# MCU_STM32F446RE.net
KiCad netlist of a schematic drawn in Altium Designer
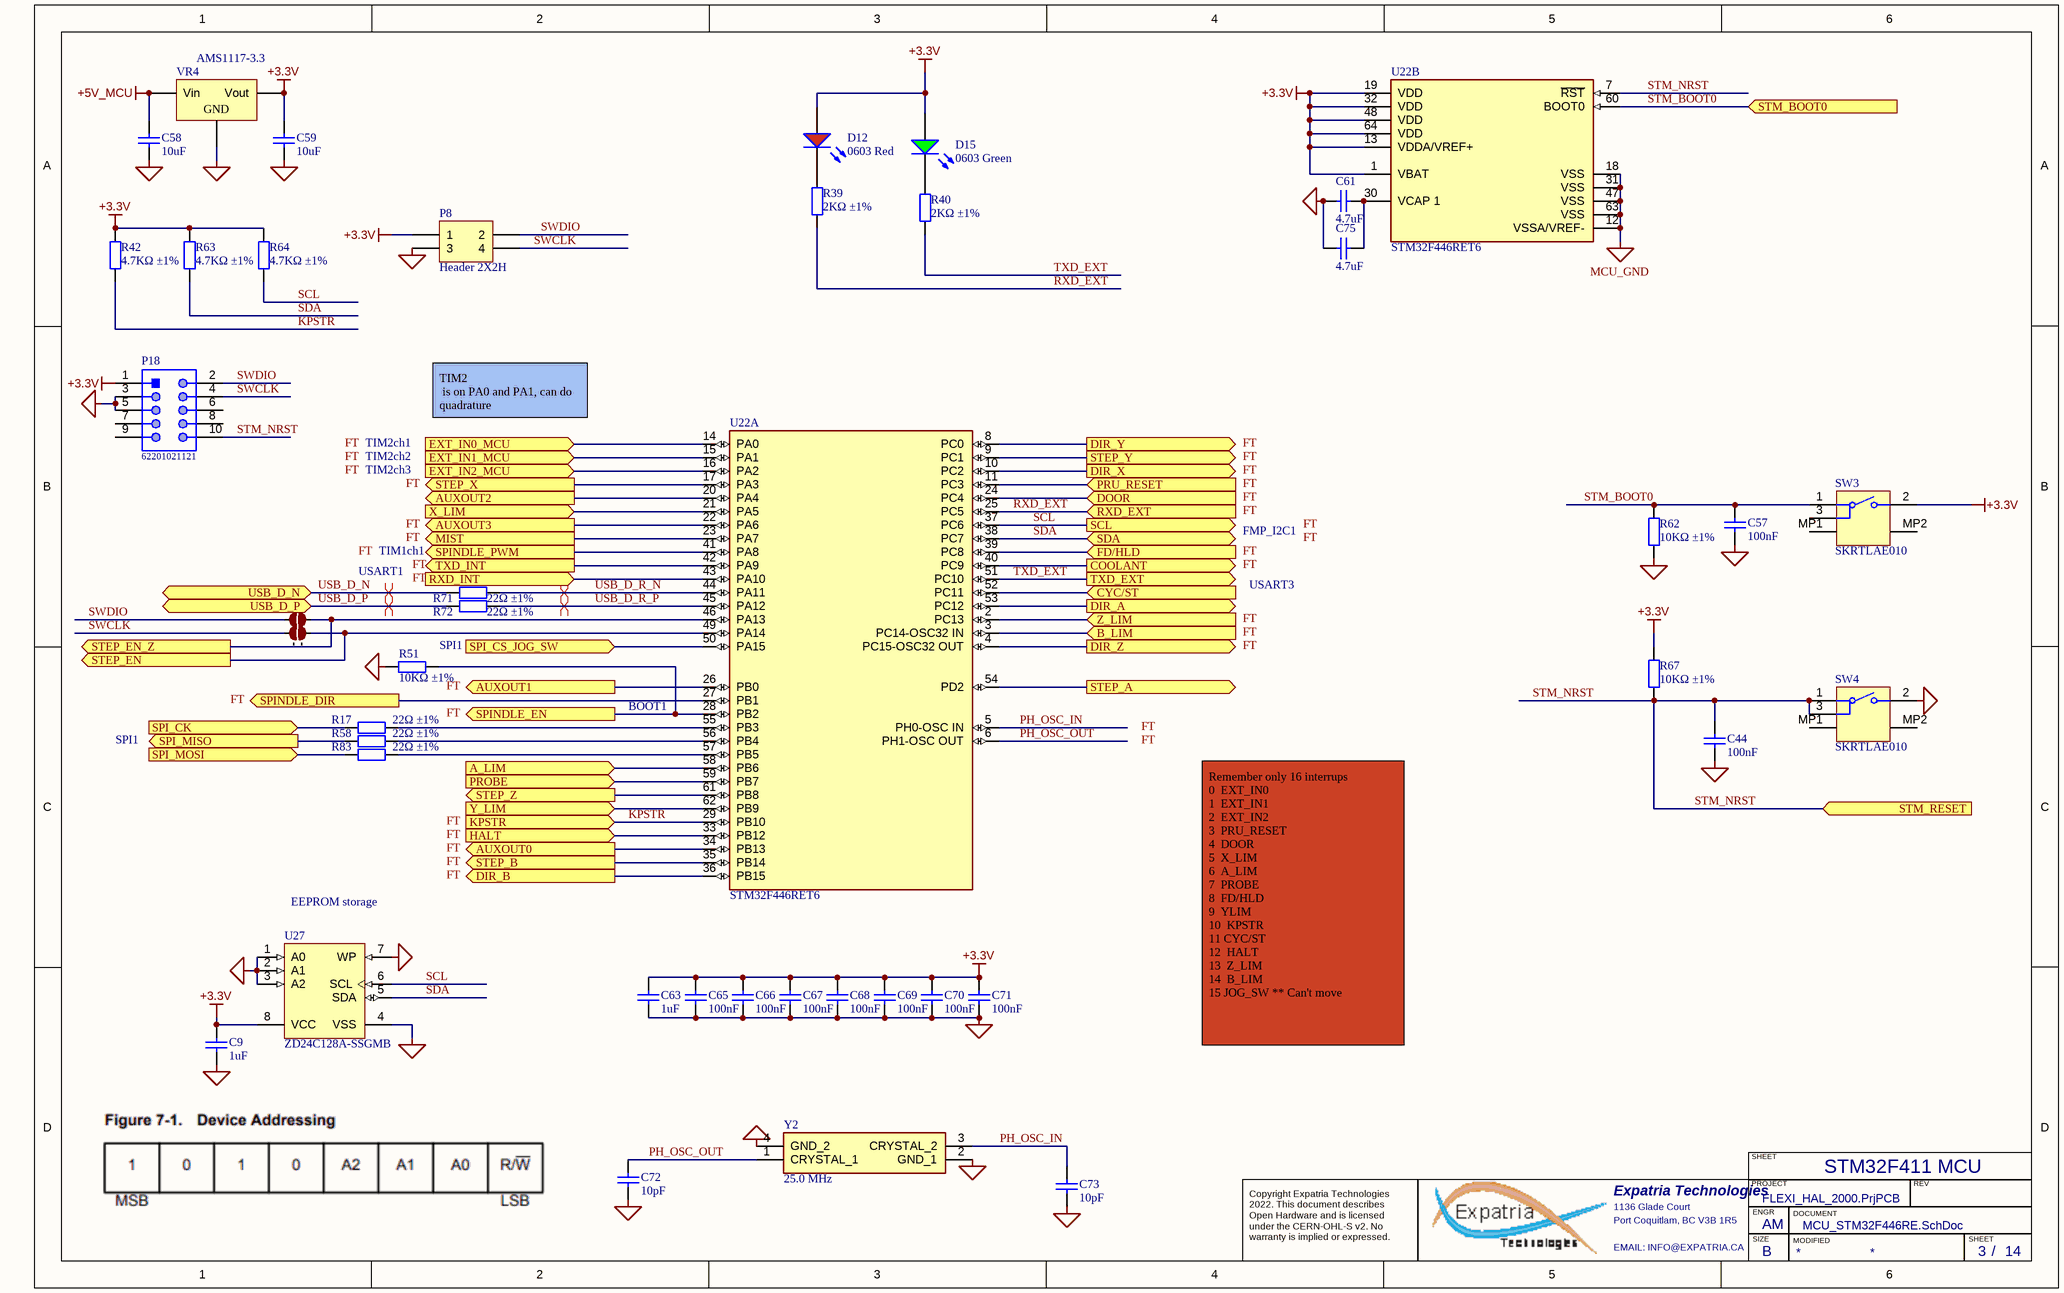
[diagram p0: MCU_STM32F446RE.SchDoc]

(export (version "E")
  (design (tool "Eeschema 10.0.6"))
  (components
    (comp (ref "C9")
      (value "1uF")
      (footprint "0603_C")
      (description "Chip capacitors")
      (fields
        (field (name "MANUFACTURER") "Samsung Electro-Mechanics")
        (field (name "PARTNUMBER") "CL10A105KB8NNNC")
      )
      (libsource (lib "Cap") (part "0603 1uF (105) 10% 50V"))
    )
    (comp (ref "C44")
      (value "100nF")
      (footprint "0603_C")
      (description "Chip capacitors")
      (fields (field (name "MANUFACTURER") "YAGEO") (field (name "PARTNUMBER") "CC0603KRX7R9BB104"))
      (libsource (lib "Cap") (part "0603 100nF (104) 10% 50V"))
    )
    (comp (ref "C57")
      (value "100nF")
      (footprint "0603_C")
      (description "Chip capacitors")
      (fields (field (name "MANUFACTURER") "YAGEO") (field (name "PARTNUMBER") "CC0603KRX7R9BB104"))
      (libsource (lib "Cap") (part "0603 100nF (104) 10% 50V"))
    )
    (comp (ref "C58")
      (value "10uF")
      (footprint "1206_C")
      (description "Chip capacitors")
      (fields
        (field (name "MANUFACTURER") "Samsung Electro-Mechanics")
        (field (name "PARTNUMBER") "CL31A106KBHNNNE")
      )
      (libsource (lib "Cap") (part "1206 10uF (106) 10% 50V"))
    )
    (comp (ref "C59")
      (value "10uF")
      (footprint "1206_C")
      (description "Chip capacitors")
      (fields
        (field (name "MANUFACTURER") "Samsung Electro-Mechanics")
        (field (name "PARTNUMBER") "CL31A106KBHNNNE")
      )
      (libsource (lib "Cap") (part "1206 10uF (106) 10% 50V"))
    )
    (comp (ref "C61")
      (value "4.7uF")
      (footprint "0603_C")
      (description "Chip capacitors")
      (fields
        (field (name "MANUFACTURER") "Samsung Electro-Mechanics")
        (field (name "PARTNUMBER") "CL10A475KO8NNNC")
      )
      (libsource (lib "Cap") (part "0603 4.7uF (475) 10% 16V"))
    )
    (comp (ref "C63")
      (value "1uF")
      (footprint "0603_C")
      (description "Chip capacitors")
      (fields
        (field (name "MANUFACTURER") "Samsung Electro-Mechanics")
        (field (name "PARTNUMBER") "CL10A105KB8NNNC")
      )
      (libsource (lib "Cap") (part "0603 1uF (105) 10% 50V"))
    )
    (comp (ref "C65")
      (value "100nF")
      (footprint "0603_C")
      (description "Chip capacitors")
      (fields (field (name "MANUFACTURER") "YAGEO") (field (name "PARTNUMBER") "CC0603KRX7R9BB104"))
      (libsource (lib "Cap") (part "0603 100nF (104) 10% 50V"))
    )
    (comp (ref "C66")
      (value "100nF")
      (footprint "0603_C")
      (description "Chip capacitors")
      (fields (field (name "MANUFACTURER") "YAGEO") (field (name "PARTNUMBER") "CC0603KRX7R9BB104"))
      (libsource (lib "Cap") (part "0603 100nF (104) 10% 50V"))
    )
    (comp (ref "C67")
      (value "100nF")
      (footprint "0603_C")
      (description "Chip capacitors")
      (fields (field (name "MANUFACTURER") "YAGEO") (field (name "PARTNUMBER") "CC0603KRX7R9BB104"))
      (libsource (lib "Cap") (part "0603 100nF (104) 10% 50V"))
    )
    (comp (ref "C68")
      (value "100nF")
      (footprint "0603_C")
      (description "Chip capacitors")
      (fields (field (name "MANUFACTURER") "YAGEO") (field (name "PARTNUMBER") "CC0603KRX7R9BB104"))
      (libsource (lib "Cap") (part "0603 100nF (104) 10% 50V"))
    )
    (comp (ref "C69")
      (value "100nF")
      (footprint "0603_C")
      (description "Chip capacitors")
      (fields (field (name "MANUFACTURER") "YAGEO") (field (name "PARTNUMBER") "CC0603KRX7R9BB104"))
      (libsource (lib "Cap") (part "0603 100nF (104) 10% 50V"))
    )
    (comp (ref "C70")
      (value "100nF")
      (footprint "0603_C")
      (description "Chip capacitors")
      (fields (field (name "MANUFACTURER") "YAGEO") (field (name "PARTNUMBER") "CC0603KRX7R9BB104"))
      (libsource (lib "Cap") (part "0603 100nF (104) 10% 50V"))
    )
    (comp (ref "C71")
      (value "100nF")
      (footprint "0603_C")
      (description "Chip capacitors")
      (fields (field (name "MANUFACTURER") "YAGEO") (field (name "PARTNUMBER") "CC0603KRX7R9BB104"))
      (libsource (lib "Cap") (part "0603 100nF (104) 10% 50V"))
    )
    (comp (ref "C72")
      (value "10pF")
      (footprint "0603_C")
      (description "Chip capacitors")
      (fields
        (field (name "MANUFACTURER") "Samsung Electro-Mechanics")
        (field (name "PARTNUMBER") "CL10C100JB8NNNC")
      )
      (libsource (lib "Cap") (part "0603 10pF (100) 5% 50V"))
    )
    (comp (ref "C73")
      (value "10pF")
      (footprint "0603_C")
      (description "Chip capacitors")
      (fields
        (field (name "MANUFACTURER") "Samsung Electro-Mechanics")
        (field (name "PARTNUMBER") "CL10C100JB8NNNC")
      )
      (libsource (lib "Cap") (part "0603 10pF (100) 5% 50V"))
    )
    (comp (ref "C75")
      (value "4.7uF")
      (footprint "0603_C")
      (description "Chip capacitors")
      (fields
        (field (name "MANUFACTURER") "Samsung Electro-Mechanics")
        (field (name "PARTNUMBER") "CL10A475KO8NNNC")
      )
      (libsource (lib "Cap") (part "0603 4.7uF (475) 10% 16V"))
    )
    (comp (ref "D12")
      (value "0603 Red")
      (footprint "0603_LED_S1")
      (description "LED")
      (libsource (lib "LED") (part "0603 LED Red"))
    )
    (comp (ref "D15")
      (value "0603 Green")
      (footprint "0603_LED_S1")
      (description "LED")
      (libsource (lib "LED") (part "0603 LED Green"))
    )
    (comp (ref "J10")
      (value "2 way net solder junction - Normally Open")
      (footprint "2waySolder_NO")
      (libsource (lib "PrintNC_GRBLHAL_Breakout") (part "2waySolderNO"))
    )
    (comp (ref "J11")
      (value "2 way net solder junction - Normally Open")
      (footprint "2waySolder_NO")
      (libsource (lib "PrintNC_GRBLHAL_Breakout") (part "2waySolderNO"))
    )
    (comp (ref "P8")
      (value "Header 2X2H")
      (footprint "HDR2X2H")
      (description "Header, 2-Pin, Dual row, Right Angle")
      (fields (field (name "PUBLISHER") "Altium Limited"))
      (libsource (lib "Miscellaneous Connectors") (part "Header 2X2H"))
    )
    (comp (ref "P18")
      (value "62201021121")
      (footprint "62201021121")
      (description "THT Vertical Pin Header WR-PHD, Pitch 1.27 mm, Dual Row, 10 pins")
      (fields (field (name "MANUFACTURER") "Wurth Elektronik") (field (name "PUBLISHER") "WurthElektronik"))
      (libsource (lib "Altium Content Vault") (part "WE-CN-2P-M-R10"))
    )
    (comp (ref "R17")
      (value "22Ω ±1%")
      (footprint "0603_R")
      (description "Chip resistor")
      (fields (field (name "MANUFACTURER") "Uniroyal Elec") (field (name "PARTNUMBER") "0603WAF220JT5E"))
      (libsource (lib "RES") (part "0603 22R (22R0) 1%"))
    )
    (comp (ref "R39")
      (value "2KΩ ±1%")
      (footprint "0603_R")
      (description "Chip resistor")
      (fields (field (name "MANUFACTURER") "Uniroyal Elec") (field (name "PARTNUMBER") "0603WAF2001T5E"))
      (libsource (lib "RES") (part "0603 2K (2001) 1%"))
    )
    (comp (ref "R40")
      (value "2KΩ ±1%")
      (footprint "0603_R")
      (description "Chip resistor")
      (fields (field (name "MANUFACTURER") "Uniroyal Elec") (field (name "PARTNUMBER") "0603WAF2001T5E"))
      (libsource (lib "RES") (part "0603 2K (2001) 1%"))
    )
    (comp (ref "R42")
      (value "4.7KΩ ±1%")
      (footprint "0603_R")
      (description "Chip resistor")
      (fields (field (name "MANUFACTURER") "Uniroyal Elec") (field (name "PARTNUMBER") "0603WAF4701T5E"))
      (libsource (lib "RES") (part "0603 4.7K (4701) 1%"))
    )
    (comp (ref "R51")
      (value "10KΩ ±1%")
      (footprint "0603_R")
      (description "Chip resistor")
      (fields (field (name "MANUFACTURER") "Uniroyal Elec") (field (name "PARTNUMBER") "0603WAF1002T5E"))
      (libsource (lib "") (part "0603 10K (1002) 1%_1"))
    )
    (comp (ref "R58")
      (value "22Ω ±1%")
      (footprint "0603_R")
      (description "Chip resistor")
      (fields (field (name "MANUFACTURER") "Uniroyal Elec") (field (name "PARTNUMBER") "0603WAF220JT5E"))
      (libsource (lib "RES") (part "0603 22R (22R0) 1%"))
    )
    (comp (ref "R62")
      (value "10KΩ ±1%")
      (footprint "0603_R")
      (description "Chip resistor")
      (fields (field (name "MANUFACTURER") "Uniroyal Elec") (field (name "PARTNUMBER") "0603WAF1002T5E"))
      (libsource (lib "RES") (part "0603 10K (1002) 1%"))
    )
    (comp (ref "R63")
      (value "4.7KΩ ±1%")
      (footprint "0603_R")
      (description "Chip resistor")
      (fields (field (name "MANUFACTURER") "Uniroyal Elec") (field (name "PARTNUMBER") "0603WAF4701T5E"))
      (libsource (lib "RES") (part "0603 4.7K (4701) 1%"))
    )
    (comp (ref "R64")
      (value "4.7KΩ ±1%")
      (footprint "0603_R")
      (description "Chip resistor")
      (fields (field (name "MANUFACTURER") "Uniroyal Elec") (field (name "PARTNUMBER") "0603WAF4701T5E"))
      (libsource (lib "RES") (part "0603 4.7K (4701) 1%"))
    )
    (comp (ref "R67")
      (value "10KΩ ±1%")
      (footprint "0603_R")
      (description "Chip resistor")
      (fields (field (name "MANUFACTURER") "Uniroyal Elec") (field (name "PARTNUMBER") "0603WAF1002T5E"))
      (libsource (lib "RES") (part "0603 10K (1002) 1%"))
    )
    (comp (ref "R71")
      (value "22Ω ±1%")
      (footprint "0603_R")
      (description "Chip resistor")
      (fields (field (name "MANUFACTURER") "Uniroyal Elec") (field (name "PARTNUMBER") "0603WAF220JT5E"))
      (libsource (lib "RES") (part "0603 22R (22R0) 1%"))
    )
    (comp (ref "R72")
      (value "22Ω ±1%")
      (footprint "0603_R")
      (description "Chip resistor")
      (fields (field (name "MANUFACTURER") "Uniroyal Elec") (field (name "PARTNUMBER") "0603WAF220JT5E"))
      (libsource (lib "RES") (part "0603 22R (22R0) 1%"))
    )
    (comp (ref "R83")
      (value "22Ω ±1%")
      (footprint "0603_R")
      (description "Chip resistor")
      (fields (field (name "MANUFACTURER") "Uniroyal Elec") (field (name "PARTNUMBER") "0603WAF220JT5E"))
      (libsource (lib "RES") (part "0603 22R (22R0) 1%"))
    )
    (comp (ref "SW3")
      (value "SKRTLAE010")
      (footprint "ALPS-SKRTLAE010_V")
      (description "Side Push Type, 250 V, -40 to 90 degC, 3-Pin SMD, RoHS, Tape and Reel")
      (fields (field (name "MANUFACTURER") "ALPS"))
      (libsource (lib "Altium Content Vault") (part "SW_SPST-3_A"))
    )
    (comp (ref "SW4")
      (value "SKRTLAE010")
      (footprint "ALPS-SKRTLAE010_V")
      (description "Side Push Type, 250 V, -40 to 90 degC, 3-Pin SMD, RoHS, Tape and Reel")
      (fields (field (name "MANUFACTURER") "ALPS"))
      (libsource (lib "Altium Content Vault") (part "SW_SPST-3_A"))
    )
    (comp (ref "U22")
      (value "STM32F446RET6")
      (footprint "FP-LQFP64-5W-IPC_B")
      (description "IC MCU 32BIT 512KB FLASH 64LQFP")
      (fields
        (field (name "OCTOPART") "https://octopart.com/stm32f446ret6-stmicroelectronics-52642920")
        (field (name "MANUFACTURER") "STMicroelectronics")
      )
      (libsource (lib "Universal_CNC_Breakout") (part "STM32F446RET6"))
    )
    (comp (ref "U27")
      (value "ZD24C128A-SSGMB")
      (footprint "SOIC-SN8_L")
      (description "IC EEPROM 128KBIT I2C 8SOIC")
      (libsource (lib "PrintNC_GRBLHAL_Breakout") (part "MEM-SEEPROM-34AA02-IL8"))
    )
    (comp (ref "VR4")
      (value "AMS1117-3.3")
      (footprint "SOT-223")
      (description "Vout=3.3V 1A 72dB@(120Hz) (LDO)")
      (libsource (lib "LDO") (part "SOT-223 AMS1117-3.3"))
    )
    (comp (ref "Y2")
      (value "25.0 MHz")
      (footprint "SamacSys:YSX321SL")
      (description "Crystal or Oscillator")
      (fields (field (name "MANUFACTURER_PART_NUMBER") "X322525MSB4SI"))
      (libsource (lib "*") (part "YSX321SL"))
    )
  )
  (nets
    (net (code "1") (name "+3.3V") (class "Default")
      (node (ref "C59") (pin "2") (pinfunction "2_2") (pintype "passive"))
      (node (ref "C63") (pin "2") (pinfunction "2_2") (pintype "passive"))
      (node (ref "C65") (pin "2") (pinfunction "2_2") (pintype "passive"))
      (node (ref "C66") (pin "2") (pinfunction "2_2") (pintype "passive"))
      (node (ref "C67") (pin "2") (pinfunction "2_2") (pintype "passive"))
      (node (ref "C68") (pin "2") (pinfunction "2_2") (pintype "passive"))
      (node (ref "C69") (pin "2") (pinfunction "2_2") (pintype "passive"))
      (node (ref "C70") (pin "2") (pinfunction "2_2") (pintype "passive"))
      (node (ref "C71") (pin "2") (pinfunction "2_2") (pintype "passive"))
      (node (ref "C9") (pin "2") (pinfunction "2_2") (pintype "passive"))
      (node (ref "D12") (pin "A") (pinfunction "A_A") (pintype "passive"))
      (node (ref "D15") (pin "A") (pinfunction "A_A") (pintype "passive"))
      (node (ref "P18") (pin "1") (pinfunction "1_1") (pintype "passive"))
      (node (ref "P8") (pin "1") (pinfunction "1_1") (pintype "passive"))
      (node (ref "R42") (pin "2") (pinfunction "2_2") (pintype "passive"))
      (node (ref "R63") (pin "2") (pinfunction "2_2") (pintype "passive"))
      (node (ref "R64") (pin "2") (pinfunction "2_2") (pintype "passive"))
      (node (ref "R67") (pin "1") (pinfunction "1_1") (pintype "passive"))
      (node (ref "SW3") (pin "2") (pinfunction "2_2") (pintype "passive"))
      (node (ref "U22") (pin "1") (pinfunction "VBAT_1") (pintype "power_in"))
      (node (ref "U22") (pin "13") (pinfunction "VDDA/VREF+_13") (pintype "power_in"))
      (node (ref "U22") (pin "19") (pinfunction "VDD_19") (pintype "power_in"))
      (node (ref "U22") (pin "32") (pinfunction "VDD_32") (pintype "power_in"))
      (node (ref "U22") (pin "48") (pinfunction "VDD_48") (pintype "power_in"))
      (node (ref "U22") (pin "64") (pinfunction "VDD_64") (pintype "power_in"))
      (node (ref "U27") (pin "8") (pinfunction "VCC_8") (pintype "power_in"))
      (node (ref "VR4") (pin "2") (pinfunction "Vout_2") (pintype "passive"))
    )
    (net (code "2") (name "+5V_MCU") (class "Default")
      (node (ref "C58") (pin "2") (pinfunction "2_2") (pintype "passive"))
      (node (ref "VR4") (pin "3") (pinfunction "Vin_3") (pintype "passive"))
    )
    (net (code "3") (name "/AUXOUT0") (class "Default")
      (node (ref "U22") (pin "34") (pinfunction "PB13_34") (pintype "bidirectional"))
    )
    (net (code "4") (name "/AUXOUT1") (class "Default")
      (node (ref "U22") (pin "26") (pinfunction "PB0_26") (pintype "bidirectional"))
    )
    (net (code "5") (name "/AUXOUT2") (class "Default")
      (node (ref "U22") (pin "20") (pinfunction "PA4_20") (pintype "bidirectional"))
    )
    (net (code "6") (name "/AUXOUT3") (class "Default")
      (node (ref "U22") (pin "22") (pinfunction "PA6_22") (pintype "bidirectional"))
    )
    (net (code "7") (name "/A_LIM") (class "Default")
      (node (ref "U22") (pin "58") (pinfunction "PB6_58") (pintype "bidirectional"))
    )
    (net (code "8") (name "/B_LIM") (class "Default")
      (node (ref "U22") (pin "3") (pinfunction "PC14-OSC32_IN_3") (pintype "bidirectional"))
    )
    (net (code "9") (name "/COOLANT") (class "Default")
      (node (ref "U22") (pin "40") (pinfunction "PC9_40") (pintype "bidirectional"))
    )
    (net (code "10") (name "/CYC{slash}ST") (class "Default")
      (node (ref "U22") (pin "52") (pinfunction "PC11_52") (pintype "bidirectional"))
    )
    (net (code "11") (name "/DIR_A") (class "Default")
      (node (ref "U22") (pin "53") (pinfunction "PC12_53") (pintype "bidirectional"))
    )
    (net (code "12") (name "/DIR_B") (class "Default")
      (node (ref "U22") (pin "36") (pinfunction "PB15_36") (pintype "bidirectional"))
    )
    (net (code "13") (name "/DIR_X") (class "Default")
      (node (ref "U22") (pin "10") (pinfunction "PC2_10") (pintype "bidirectional"))
    )
    (net (code "14") (name "/DIR_Y") (class "Default")
      (node (ref "U22") (pin "8") (pinfunction "PC0_8") (pintype "bidirectional"))
    )
    (net (code "15") (name "/DIR_Z") (class "Default")
      (node (ref "U22") (pin "4") (pinfunction "PC15-OSC32_OUT_4") (pintype "bidirectional"))
    )
    (net (code "16") (name "/DOOR") (class "Default")
      (node (ref "U22") (pin "24") (pinfunction "PC4_24") (pintype "bidirectional"))
    )
    (net (code "17") (name "/EXT_IN0_MCU") (class "Default")
      (node (ref "U22") (pin "14") (pinfunction "PA0_14") (pintype "bidirectional"))
    )
    (net (code "18") (name "/EXT_IN1_MCU") (class "Default")
      (node (ref "U22") (pin "15") (pinfunction "PA1_15") (pintype "bidirectional"))
    )
    (net (code "19") (name "/EXT_IN2_MCU") (class "Default")
      (node (ref "U22") (pin "16") (pinfunction "PA2_16") (pintype "bidirectional"))
    )
    (net (code "20") (name "/FD{slash}HLD") (class "Default")
      (node (ref "U22") (pin "39") (pinfunction "PC8_39") (pintype "bidirectional"))
    )
    (net (code "21") (name "/HALT") (class "Default")
      (node (ref "U22") (pin "33") (pinfunction "PB12_33") (pintype "bidirectional"))
    )
    (net (code "22") (name "/KPSTR") (class "Default")
      (node (ref "R42") (pin "1") (pinfunction "1_1") (pintype "passive"))
      (node (ref "U22") (pin "29") (pinfunction "PB10_29") (pintype "bidirectional"))
    )
    (net (code "23") (name "/MIST") (class "Default")
      (node (ref "U22") (pin "23") (pinfunction "PA7_23") (pintype "bidirectional"))
    )
    (net (code "24") (name "/PH_OSC_IN") (class "Default")
      (node (ref "C73") (pin "2") (pinfunction "2_2") (pintype "passive"))
      (node (ref "U22") (pin "5") (pinfunction "PH0-OSC_IN_5") (pintype "bidirectional"))
      (node (ref "Y2") (pin "3") (pinfunction "CRYSTAL_2_3") (pintype "passive"))
    )
    (net (code "25") (name "/PH_OSC_OUT") (class "Default")
      (node (ref "C72") (pin "2") (pinfunction "2_2") (pintype "passive"))
      (node (ref "U22") (pin "6") (pinfunction "PH1-OSC_OUT_6") (pintype "bidirectional"))
      (node (ref "Y2") (pin "1") (pinfunction "CRYSTAL_1_1") (pintype "passive"))
    )
    (net (code "26") (name "/PROBE") (class "Default")
      (node (ref "U22") (pin "59") (pinfunction "PB7_59") (pintype "bidirectional"))
    )
    (net (code "27") (name "/PRU_RESET") (class "Default")
      (node (ref "U22") (pin "11") (pinfunction "PC3_11") (pintype "bidirectional"))
    )
    (net (code "28") (name "/RXD_EXT") (class "Default")
      (node (ref "R39") (pin "1") (pinfunction "1_1") (pintype "passive"))
      (node (ref "U22") (pin "25") (pinfunction "PC5_25") (pintype "bidirectional"))
    )
    (net (code "29") (name "/RXD_INT") (class "Default")
      (node (ref "U22") (pin "43") (pinfunction "PA10_43") (pintype "bidirectional"))
    )
    (net (code "30") (name "/SCL") (class "Default")
      (node (ref "R64") (pin "1") (pinfunction "1_1") (pintype "passive"))
      (node (ref "U22") (pin "37") (pinfunction "PC6_37") (pintype "bidirectional"))
      (node (ref "U27") (pin "6") (pinfunction "SCL_6") (pintype "input"))
    )
    (net (code "31") (name "/SDA") (class "Default")
      (node (ref "R63") (pin "1") (pinfunction "1_1") (pintype "passive"))
      (node (ref "U22") (pin "38") (pinfunction "PC7_38") (pintype "bidirectional"))
      (node (ref "U27") (pin "5") (pinfunction "SDA_5") (pintype "bidirectional"))
    )
    (net (code "32") (name "/SPINDLE_DIR") (class "Default")
      (node (ref "U22") (pin "27") (pinfunction "PB1_27") (pintype "bidirectional"))
    )
    (net (code "33") (name "/SPINDLE_EN") (class "Default")
      (node (ref "R51") (pin "2") (pinfunction "2_2") (pintype "passive"))
      (node (ref "U22") (pin "28") (pinfunction "PB2_28") (pintype "bidirectional"))
    )
    (net (code "34") (name "/SPINDLE_PWM") (class "Default")
      (node (ref "U22") (pin "41") (pinfunction "PA8_41") (pintype "bidirectional"))
    )
    (net (code "35") (name "/SPI_CK") (class "Default")
      (node (ref "R17") (pin "2") (pinfunction "2_2") (pintype "passive"))
    )
    (net (code "36") (name "/SPI_CS_JOG_SW") (class "Default")
      (node (ref "U22") (pin "50") (pinfunction "PA15_50") (pintype "bidirectional"))
    )
    (net (code "37") (name "/SPI_MISO") (class "Default")
      (node (ref "R58") (pin "2") (pinfunction "2_2") (pintype "passive"))
    )
    (net (code "38") (name "/SPI_MOSI") (class "Default")
      (node (ref "R83") (pin "2") (pinfunction "2_2") (pintype "passive"))
    )
    (net (code "39") (name "/STEP_A") (class "Default")
      (node (ref "U22") (pin "54") (pinfunction "PD2_54") (pintype "bidirectional"))
    )
    (net (code "40") (name "/STEP_B") (class "Default")
      (node (ref "U22") (pin "35") (pinfunction "PB14_35") (pintype "bidirectional"))
    )
    (net (code "41") (name "/STEP_EN") (class "Default")
      (node (ref "J11") (pin "2") (pinfunction "2_2") (pintype "passive"))
      (node (ref "U22") (pin "49") (pinfunction "PA14_49") (pintype "bidirectional"))
    )
    (net (code "42") (name "/STEP_EN_Z") (class "Default")
      (node (ref "J10") (pin "2") (pinfunction "2_2") (pintype "passive"))
      (node (ref "U22") (pin "46") (pinfunction "PA13_46") (pintype "bidirectional"))
    )
    (net (code "43") (name "/STEP_X") (class "Default")
      (node (ref "U22") (pin "17") (pinfunction "PA3_17") (pintype "bidirectional"))
    )
    (net (code "44") (name "/STEP_Y") (class "Default")
      (node (ref "U22") (pin "9") (pinfunction "PC1_9") (pintype "bidirectional"))
    )
    (net (code "45") (name "/STEP_Z") (class "Default")
      (node (ref "U22") (pin "61") (pinfunction "PB8_61") (pintype "bidirectional"))
    )
    (net (code "46") (name "/STM_BOOT0") (class "Default")
      (node (ref "C57") (pin "2") (pinfunction "2_2") (pintype "passive"))
      (node (ref "R62") (pin "1") (pinfunction "1_1") (pintype "passive"))
      (node (ref "SW3") (pin "1") (pinfunction "1_1") (pintype "passive"))
      (node (ref "U22") (pin "60") (pinfunction "BOOT0_60") (pintype "input"))
    )
    (net (code "47") (name "/STM_NRST") (class "Default")
      (node (ref "C44") (pin "2") (pinfunction "2_2") (pintype "passive"))
      (node (ref "P18") (pin "10") (pinfunction "10_10") (pintype "passive"))
      (node (ref "R67") (pin "2") (pinfunction "2_2") (pintype "passive"))
      (node (ref "SW4") (pin "1") (pinfunction "1_1") (pintype "passive"))
      (node (ref "SW4") (pin "3") (pinfunction "3_3") (pintype "passive"))
      (node (ref "U22") (pin "7") (pinfunction "~{RST}_7") (pintype "input"))
    )
    (net (code "48") (name "/SWCLK") (class "Default")
      (node (ref "J11") (pin "1") (pinfunction "1_1") (pintype "passive"))
      (node (ref "P18") (pin "4") (pinfunction "4_4") (pintype "passive"))
      (node (ref "P8") (pin "4") (pinfunction "4_4") (pintype "passive"))
    )
    (net (code "49") (name "/SWDIO") (class "Default")
      (node (ref "J10") (pin "1") (pinfunction "1_1") (pintype "passive"))
      (node (ref "P18") (pin "2") (pinfunction "2_2") (pintype "passive"))
      (node (ref "P8") (pin "2") (pinfunction "2_2") (pintype "passive"))
    )
    (net (code "50") (name "/TXD_EXT") (class "Default")
      (node (ref "R40") (pin "1") (pinfunction "1_1") (pintype "passive"))
      (node (ref "U22") (pin "51") (pinfunction "PC10_51") (pintype "bidirectional"))
    )
    (net (code "51") (name "/TXD_INT") (class "Default")
      (node (ref "U22") (pin "42") (pinfunction "PA9_42") (pintype "bidirectional"))
    )
    (net (code "52") (name "/USB_D_N") (class "Default")
      (node (ref "R71") (pin "2") (pinfunction "2_2") (pintype "passive"))
    )
    (net (code "53") (name "/USB_D_P") (class "Default")
      (node (ref "R72") (pin "2") (pinfunction "2_2") (pintype "passive"))
    )
    (net (code "54") (name "/USB_D_R_N") (class "Default")
      (node (ref "R71") (pin "1") (pinfunction "1_1") (pintype "passive"))
      (node (ref "U22") (pin "44") (pinfunction "PA11_44") (pintype "bidirectional"))
    )
    (net (code "55") (name "/USB_D_R_P") (class "Default")
      (node (ref "R72") (pin "1") (pinfunction "1_1") (pintype "passive"))
      (node (ref "U22") (pin "45") (pinfunction "PA12_45") (pintype "bidirectional"))
    )
    (net (code "56") (name "/X_LIM") (class "Default")
      (node (ref "U22") (pin "21") (pinfunction "PA5_21") (pintype "bidirectional"))
    )
    (net (code "57") (name "/Y_LIM") (class "Default")
      (node (ref "U22") (pin "62") (pinfunction "PB9_62") (pintype "bidirectional"))
    )
    (net (code "58") (name "/Z_LIM") (class "Default")
      (node (ref "U22") (pin "2") (pinfunction "PC13_2") (pintype "bidirectional"))
    )
    (net (code "59") (name "MCU_GND") (class "Default")
      (node (ref "C44") (pin "1") (pinfunction "1_1") (pintype "passive"))
      (node (ref "C57") (pin "1") (pinfunction "1_1") (pintype "passive"))
      (node (ref "C58") (pin "1") (pinfunction "1_1") (pintype "passive"))
      (node (ref "C59") (pin "1") (pinfunction "1_1") (pintype "passive"))
      (node (ref "C61") (pin "1") (pinfunction "1_1") (pintype "passive"))
      (node (ref "C63") (pin "1") (pinfunction "1_1") (pintype "passive"))
      (node (ref "C65") (pin "1") (pinfunction "1_1") (pintype "passive"))
      (node (ref "C66") (pin "1") (pinfunction "1_1") (pintype "passive"))
      (node (ref "C67") (pin "1") (pinfunction "1_1") (pintype "passive"))
      (node (ref "C68") (pin "1") (pinfunction "1_1") (pintype "passive"))
      (node (ref "C69") (pin "1") (pinfunction "1_1") (pintype "passive"))
      (node (ref "C70") (pin "1") (pinfunction "1_1") (pintype "passive"))
      (node (ref "C71") (pin "1") (pinfunction "1_1") (pintype "passive"))
      (node (ref "C72") (pin "1") (pinfunction "1_1") (pintype "passive"))
      (node (ref "C73") (pin "1") (pinfunction "1_1") (pintype "passive"))
      (node (ref "C75") (pin "1") (pinfunction "1_1") (pintype "passive"))
      (node (ref "C9") (pin "1") (pinfunction "1_1") (pintype "passive"))
      (node (ref "P18") (pin "3") (pinfunction "3_3") (pintype "passive"))
      (node (ref "P18") (pin "5") (pinfunction "5_5") (pintype "passive"))
      (node (ref "P8") (pin "3") (pinfunction "3_3") (pintype "passive"))
      (node (ref "R51") (pin "1") (pinfunction "1_1") (pintype "passive"))
      (node (ref "R62") (pin "2") (pinfunction "2_2") (pintype "passive"))
      (node (ref "SW4") (pin "2") (pinfunction "2_2") (pintype "passive"))
      (node (ref "U22") (pin "12") (pinfunction "VSSA/VREF-_12") (pintype "power_in"))
      (node (ref "U22") (pin "18") (pinfunction "VSS_18") (pintype "power_in"))
      (node (ref "U22") (pin "31") (pinfunction "VSS_31") (pintype "power_in"))
      (node (ref "U22") (pin "47") (pinfunction "VSS_47") (pintype "power_in"))
      (node (ref "U22") (pin "63") (pinfunction "VSS_63") (pintype "power_in"))
      (node (ref "U27") (pin "1") (pinfunction "A0_1") (pintype "input"))
      (node (ref "U27") (pin "2") (pinfunction "A1_2") (pintype "input"))
      (node (ref "U27") (pin "3") (pinfunction "A2_3") (pintype "input"))
      (node (ref "U27") (pin "4") (pinfunction "VSS_4") (pintype "power_in"))
      (node (ref "U27") (pin "7") (pinfunction "WP_7") (pintype "input"))
      (node (ref "VR4") (pin "1") (pinfunction "GND_1") (pintype "passive"))
      (node (ref "Y2") (pin "2") (pinfunction "GND_1_2") (pintype "passive"))
      (node (ref "Y2") (pin "4") (pinfunction "GND_2_4") (pintype "passive"))
    )
    (net (code "60") (name "Net-(D12-PadK)") (class "Default")
      (node (ref "D12") (pin "K") (pinfunction "K_K") (pintype "passive"))
      (node (ref "R39") (pin "2") (pinfunction "2_2") (pintype "passive"))
    )
    (net (code "61") (name "Net-(D15-PadK)") (class "Default")
      (node (ref "D15") (pin "K") (pinfunction "K_K") (pintype "passive"))
      (node (ref "R40") (pin "2") (pinfunction "2_2") (pintype "passive"))
    )
    (net (code "62") (name "Net-(U22A-PB3)") (class "Default")
      (node (ref "R17") (pin "1") (pinfunction "1_1") (pintype "passive"))
      (node (ref "U22") (pin "55") (pinfunction "PB3_55") (pintype "bidirectional"))
    )
    (net (code "63") (name "Net-(U22A-PB4)") (class "Default")
      (node (ref "R58") (pin "1") (pinfunction "1_1") (pintype "passive"))
      (node (ref "U22") (pin "56") (pinfunction "PB4_56") (pintype "bidirectional"))
    )
    (net (code "64") (name "Net-(U22A-PB5)") (class "Default")
      (node (ref "R83") (pin "1") (pinfunction "1_1") (pintype "passive"))
      (node (ref "U22") (pin "57") (pinfunction "PB5_57") (pintype "bidirectional"))
    )
    (net (code "65") (name "Net-(U22B-VCAP_1)") (class "Default")
      (node (ref "C61") (pin "2") (pinfunction "2_2") (pintype "passive"))
      (node (ref "C75") (pin "2") (pinfunction "2_2") (pintype "passive"))
      (node (ref "U22") (pin "30") (pinfunction "VCAP_1_30") (pintype "power_in"))
    )
    (net (code "66") (name "unconnected-(P18-Pad6)") (class "Default")
      (node (ref "P18") (pin "6") (pinfunction "6_6") (pintype "passive"))
    )
    (net (code "67") (name "unconnected-(P18-Pad7)") (class "Default")
      (node (ref "P18") (pin "7") (pinfunction "7_7") (pintype "passive"))
    )
    (net (code "68") (name "unconnected-(P18-Pad8)") (class "Default")
      (node (ref "P18") (pin "8") (pinfunction "8_8") (pintype "passive"))
    )
    (net (code "69") (name "unconnected-(P18-Pad9)") (class "Default")
      (node (ref "P18") (pin "9") (pinfunction "9_9") (pintype "passive"))
    )
    (net (code "70") (name "unconnected-(SW3-Pad3)") (class "Default")
      (node (ref "SW3") (pin "3") (pinfunction "3_3") (pintype "passive"))
    )
    (net (code "71") (name "unconnected-(SW3-PadMP1)") (class "Default")
      (node (ref "SW3") (pin "MP1") (pinfunction "MP1_MP1") (pintype "passive"))
    )
    (net (code "72") (name "unconnected-(SW3-PadMP2)") (class "Default")
      (node (ref "SW3") (pin "MP2") (pinfunction "MP2_MP2") (pintype "passive"))
    )
    (net (code "73") (name "unconnected-(SW4-PadMP1)") (class "Default")
      (node (ref "SW4") (pin "MP1") (pinfunction "MP1_MP1") (pintype "passive"))
    )
    (net (code "74") (name "unconnected-(SW4-PadMP2)") (class "Default")
      (node (ref "SW4") (pin "MP2") (pinfunction "MP2_MP2") (pintype "passive"))
    )
  )
)
